# GNNS.net
KiCad netlist of a schematic drawn in Altium Designer
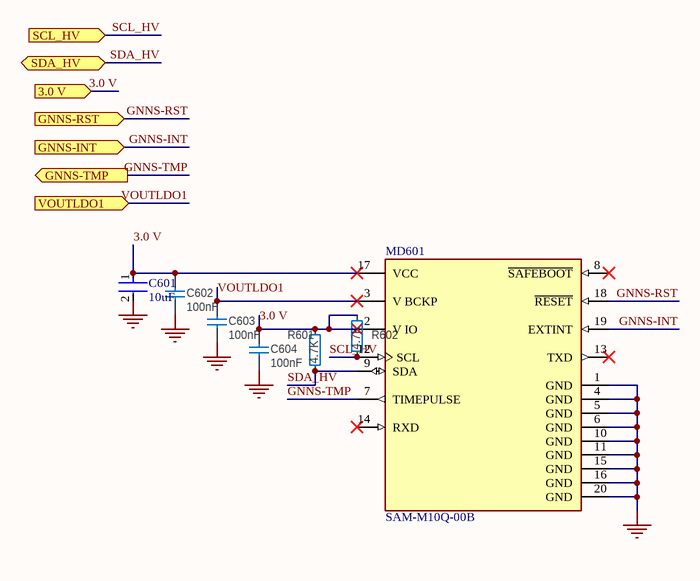
[diagram p0: GNNS (SAM-M10Q-00B).SchDoc]

(export (version "E")
  (design (tool "Eeschema 10.0.6"))
  (components
    (comp (ref "C601")
      (value "10uF")
      (footprint "FP-GRM188-0_2-MFG")
      (description "Chip Multilayer Ceramic Capacitors for General Purpose, 0603, 10uF, X5R, 15%, 20%, 25V")
      (fields (field (name "TOLERANCE") "20%") (field (name "VOLTAGE") "25V"))
      (libsource (lib "Altium Content Vault") (part "11868f565c42a9108669ba33697ecf6"))
    )
    (comp (ref "C602")
      (value "100nF")
      (footprint "CAPC0603X03L_C")
      (description "Capacitor, X7S, ±10%")
      (fields (field (name "AUTHOR") "rsk"))
      (libsource (lib "Watch_Components") (part "C0201-100n-16V-X7S"))
    )
    (comp (ref "C603")
      (value "100nF")
      (footprint "CAPC0603X03L_C")
      (description "Capacitor, X7S, ±10%")
      (fields (field (name "AUTHOR") "rsk"))
      (libsource (lib "Watch_Components") (part "C0201-100n-16V-X7S"))
    )
    (comp (ref "C604")
      (value "100nF")
      (footprint "CAPC0603X03L_C")
      (description "Capacitor, X7S, ±10%")
      (fields (field (name "AUTHOR") "rsk"))
      (libsource (lib "Watch_Components") (part "C0201-100n-16V-X7S"))
    )
    (comp (ref "MD601")
      (value "SAM-M10Q-00B")
      (footprint "FP-SAM-M10Q-00B-MFG")
      (description "M10 GNSS LGA PATCH ANTENNA MOD")
      (libsource (lib "Altium Content Vault") (part "1cb72461910aa5e6ea511d063e6c758"))
    )
    (comp (ref "R601")
      (value "4.7K")
      (footprint "RESC0603X03L_C")
      (description "Resistor, ±1%, 0.05W")
      (fields
        (field (name "PART NUMBER") "R0201-10k")
        (field (name "MANUFACTURER") "N.A.")
        (field (name "AUTHOR") "rsk")
      )
      (libsource (lib "AltiumLib") (part "RES"))
    )
    (comp (ref "R602")
      (value "4.7K")
      (footprint "RESC0603X03L_C")
      (description "Resistor, ±1%, 0.05W")
      (fields
        (field (name "PART NUMBER") "R0201-10k")
        (field (name "MANUFACTURER") "N.A.")
        (field (name "AUTHOR") "rsk")
      )
      (libsource (lib "AltiumLib") (part "RES"))
    )
  )
  (nets
    (net (code "1") (name "/3.0 V") (class "Default")
      (node (ref "C601") (pin "1") (pinfunction "1_1") (pintype "passive"))
      (node (ref "C602") (pin "2") (pinfunction "2_2") (pintype "passive"))
      (node (ref "C604") (pin "2") (pinfunction "2_2") (pintype "passive"))
      (node (ref "MD601") (pin "17") (pinfunction "VCC_17") (pintype "power_in"))
      (node (ref "MD601") (pin "2") (pinfunction "V_IO_2") (pintype "power_in"))
      (node (ref "R601") (pin "1") (pinfunction "1_1") (pintype "passive"))
      (node (ref "R602") (pin "1") (pinfunction "1_1") (pintype "passive"))
    )
    (net (code "2") (name "/GNNS-INT") (class "Default")
      (node (ref "MD601") (pin "19") (pinfunction "EXTINT_19") (pintype "input"))
    )
    (net (code "3") (name "/GNNS-RST") (class "Default")
      (node (ref "MD601") (pin "18") (pinfunction "~{RESET}_18") (pintype "input"))
    )
    (net (code "4") (name "/GNNS-TMP") (class "Default")
      (node (ref "MD601") (pin "7") (pinfunction "TIMEPULSE_7") (pintype "output"))
    )
    (net (code "5") (name "/SCL_HV") (class "Default")
      (node (ref "MD601") (pin "12") (pinfunction "SCL_12") (pintype "input"))
      (node (ref "R602") (pin "2") (pinfunction "2_2") (pintype "passive"))
    )
    (net (code "6") (name "/SDA_HV") (class "Default")
      (node (ref "MD601") (pin "9") (pinfunction "SDA_9") (pintype "bidirectional"))
      (node (ref "R601") (pin "2") (pinfunction "2_2") (pintype "passive"))
    )
    (net (code "7") (name "/VOUTLDO1") (class "Default")
      (node (ref "C603") (pin "2") (pinfunction "2_2") (pintype "passive"))
      (node (ref "MD601") (pin "3") (pinfunction "V_BCKP_3") (pintype "power_in"))
    )
    (net (code "8") (name "GND") (class "Default")
      (node (ref "C601") (pin "2") (pinfunction "2_2") (pintype "passive"))
      (node (ref "C602") (pin "1") (pinfunction "1_1") (pintype "passive"))
      (node (ref "C603") (pin "1") (pinfunction "1_1") (pintype "passive"))
      (node (ref "C604") (pin "1") (pinfunction "1_1") (pintype "passive"))
      (node (ref "MD601") (pin "1") (pinfunction "GND_1") (pintype "power_in"))
      (node (ref "MD601") (pin "10") (pinfunction "GND_10") (pintype "power_in"))
      (node (ref "MD601") (pin "11") (pinfunction "GND_11") (pintype "power_in"))
      (node (ref "MD601") (pin "15") (pinfunction "GND_15") (pintype "power_in"))
      (node (ref "MD601") (pin "16") (pinfunction "GND_16") (pintype "power_in"))
      (node (ref "MD601") (pin "20") (pinfunction "GND_20") (pintype "power_in"))
      (node (ref "MD601") (pin "4") (pinfunction "GND_4") (pintype "power_in"))
      (node (ref "MD601") (pin "5") (pinfunction "GND_5") (pintype "power_in"))
      (node (ref "MD601") (pin "6") (pinfunction "GND_6") (pintype "power_in"))
    )
    (net (code "9") (name "unconnected-(MD601-RXD-Pad14)") (class "Default")
      (node (ref "MD601") (pin "14") (pinfunction "RXD_14") (pintype "input+no_connect"))
    )
    (net (code "10") (name "unconnected-(MD601-TXD-Pad13)") (class "Default")
      (node (ref "MD601") (pin "13") (pinfunction "TXD_13") (pintype "output+no_connect"))
    )
    (net (code "11") (name "unconnected-(MD601-~{SAFEBOOT}-Pad8)") (class "Default")
      (node (ref "MD601") (pin "8") (pinfunction "~{SAFEBOOT}_8") (pintype "input+no_connect"))
    )
  )
)
